# RoboRio_LED_THOLE_schematic.net
KiCad netlist of a schematic drawn in EAGLE
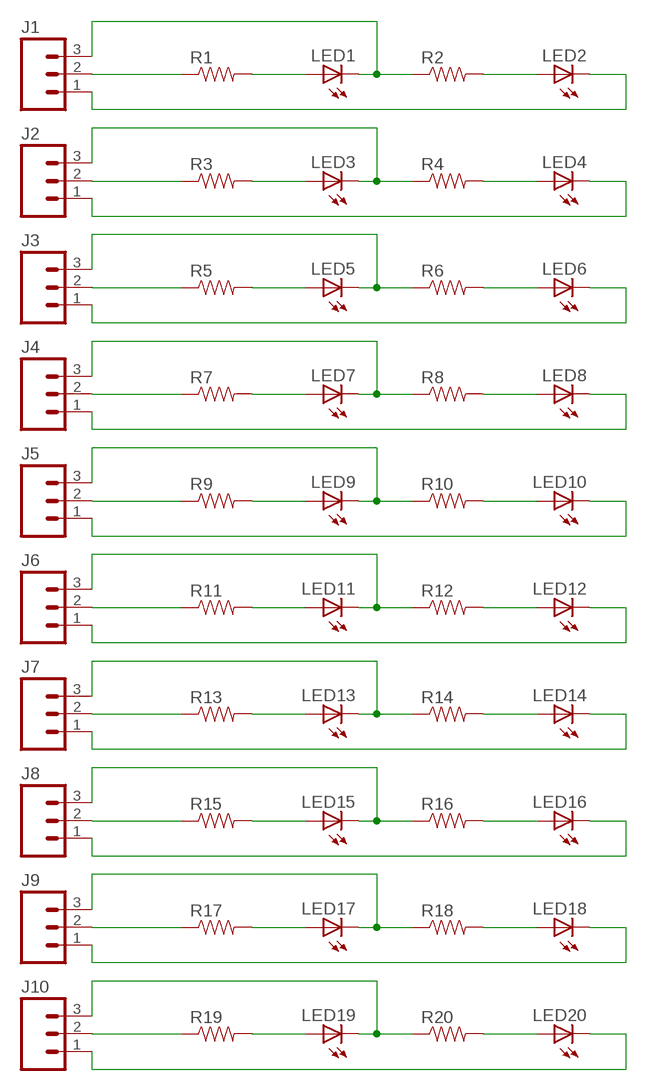
[diagram p0: schematic, sheet 1]

(export (version "E")
  (design (tool "Eeschema 10.0.6"))
  (components
    (comp (ref "J1")
      (value "M03PTH")
      (footprint "eagle-import:1X03")
      (libsource (lib "eagle-import") (part "M03PTH"))
    )
    (comp (ref "J2")
      (value "M03PTH")
      (footprint "eagle-import:1X03")
      (libsource (lib "eagle-import") (part "M03PTH"))
    )
    (comp (ref "J3")
      (value "M03PTH")
      (footprint "eagle-import:1X03")
      (libsource (lib "eagle-import") (part "M03PTH"))
    )
    (comp (ref "J4")
      (value "M03PTH")
      (footprint "eagle-import:1X03")
      (libsource (lib "eagle-import") (part "M03PTH"))
    )
    (comp (ref "J5")
      (value "M03PTH")
      (footprint "eagle-import:1X03")
      (libsource (lib "eagle-import") (part "M03PTH"))
    )
    (comp (ref "J6")
      (value "M03PTH")
      (footprint "eagle-import:1X03")
      (libsource (lib "eagle-import") (part "M03PTH"))
    )
    (comp (ref "J7")
      (value "M03PTH")
      (footprint "eagle-import:1X03")
      (libsource (lib "eagle-import") (part "M03PTH"))
    )
    (comp (ref "J8")
      (value "M03PTH")
      (footprint "eagle-import:1X03")
      (libsource (lib "eagle-import") (part "M03PTH"))
    )
    (comp (ref "J9")
      (value "M03PTH")
      (footprint "eagle-import:1X03")
      (libsource (lib "eagle-import") (part "M03PTH"))
    )
    (comp (ref "J10")
      (value "M03PTH")
      (footprint "eagle-import:1X03")
      (libsource (lib "eagle-import") (part "M03PTH"))
    )
    (comp (ref "LED1")
      (value "LED3MM")
      (footprint "eagle-import:LED3MM")
      (libsource (lib "eagle-import") (part "LED3MM"))
    )
    (comp (ref "LED2")
      (value "LED3MM")
      (footprint "eagle-import:LED3MM")
      (libsource (lib "eagle-import") (part "LED3MM"))
    )
    (comp (ref "LED3")
      (value "LED3MM")
      (footprint "eagle-import:LED3MM")
      (libsource (lib "eagle-import") (part "LED3MM"))
    )
    (comp (ref "LED4")
      (value "LED3MM")
      (footprint "eagle-import:LED3MM")
      (libsource (lib "eagle-import") (part "LED3MM"))
    )
    (comp (ref "LED5")
      (value "LED3MM")
      (footprint "eagle-import:LED3MM")
      (libsource (lib "eagle-import") (part "LED3MM"))
    )
    (comp (ref "LED6")
      (value "LED3MM")
      (footprint "eagle-import:LED3MM")
      (libsource (lib "eagle-import") (part "LED3MM"))
    )
    (comp (ref "LED7")
      (value "LED3MM")
      (footprint "eagle-import:LED3MM")
      (libsource (lib "eagle-import") (part "LED3MM"))
    )
    (comp (ref "LED8")
      (value "LED3MM")
      (footprint "eagle-import:LED3MM")
      (libsource (lib "eagle-import") (part "LED3MM"))
    )
    (comp (ref "LED9")
      (value "LED3MM")
      (footprint "eagle-import:LED3MM")
      (libsource (lib "eagle-import") (part "LED3MM"))
    )
    (comp (ref "LED10")
      (value "LED3MM")
      (footprint "eagle-import:LED3MM")
      (libsource (lib "eagle-import") (part "LED3MM"))
    )
    (comp (ref "LED11")
      (value "LED3MM")
      (footprint "eagle-import:LED3MM")
      (libsource (lib "eagle-import") (part "LED3MM"))
    )
    (comp (ref "LED12")
      (value "LED3MM")
      (footprint "eagle-import:LED3MM")
      (libsource (lib "eagle-import") (part "LED3MM"))
    )
    (comp (ref "LED13")
      (value "LED3MM")
      (footprint "eagle-import:LED3MM")
      (libsource (lib "eagle-import") (part "LED3MM"))
    )
    (comp (ref "LED14")
      (value "LED3MM")
      (footprint "eagle-import:LED3MM")
      (libsource (lib "eagle-import") (part "LED3MM"))
    )
    (comp (ref "LED15")
      (value "LED3MM")
      (footprint "eagle-import:LED3MM")
      (libsource (lib "eagle-import") (part "LED3MM"))
    )
    (comp (ref "LED16")
      (value "LED3MM")
      (footprint "eagle-import:LED3MM")
      (libsource (lib "eagle-import") (part "LED3MM"))
    )
    (comp (ref "LED17")
      (value "LED3MM")
      (footprint "eagle-import:LED3MM")
      (libsource (lib "eagle-import") (part "LED3MM"))
    )
    (comp (ref "LED18")
      (value "LED3MM")
      (footprint "eagle-import:LED3MM")
      (libsource (lib "eagle-import") (part "LED3MM"))
    )
    (comp (ref "LED19")
      (value "LED3MM")
      (footprint "eagle-import:LED3MM")
      (libsource (lib "eagle-import") (part "LED3MM"))
    )
    (comp (ref "LED20")
      (value "LED3MM")
      (footprint "eagle-import:LED3MM")
      (libsource (lib "eagle-import") (part "LED3MM"))
    )
    (comp (ref "R1")
      (value "RESISTORKIT")
      (footprint "eagle-import:AXIAL-0.3-KIT")
      (libsource (lib "eagle-import") (part "RESISTORKIT"))
    )
    (comp (ref "R2")
      (value "RESISTORKIT")
      (footprint "eagle-import:AXIAL-0.3-KIT")
      (libsource (lib "eagle-import") (part "RESISTORKIT"))
    )
    (comp (ref "R3")
      (value "RESISTORKIT")
      (footprint "eagle-import:AXIAL-0.3-KIT")
      (libsource (lib "eagle-import") (part "RESISTORKIT"))
    )
    (comp (ref "R4")
      (value "RESISTORKIT")
      (footprint "eagle-import:AXIAL-0.3-KIT")
      (libsource (lib "eagle-import") (part "RESISTORKIT"))
    )
    (comp (ref "R5")
      (value "RESISTORKIT")
      (footprint "eagle-import:AXIAL-0.3-KIT")
      (libsource (lib "eagle-import") (part "RESISTORKIT"))
    )
    (comp (ref "R6")
      (value "RESISTORKIT")
      (footprint "eagle-import:AXIAL-0.3-KIT")
      (libsource (lib "eagle-import") (part "RESISTORKIT"))
    )
    (comp (ref "R7")
      (value "RESISTORKIT")
      (footprint "eagle-import:AXIAL-0.3-KIT")
      (libsource (lib "eagle-import") (part "RESISTORKIT"))
    )
    (comp (ref "R8")
      (value "RESISTORKIT")
      (footprint "eagle-import:AXIAL-0.3-KIT")
      (libsource (lib "eagle-import") (part "RESISTORKIT"))
    )
    (comp (ref "R9")
      (value "RESISTORKIT")
      (footprint "eagle-import:AXIAL-0.3-KIT")
      (libsource (lib "eagle-import") (part "RESISTORKIT"))
    )
    (comp (ref "R10")
      (value "RESISTORKIT")
      (footprint "eagle-import:AXIAL-0.3-KIT")
      (libsource (lib "eagle-import") (part "RESISTORKIT"))
    )
    (comp (ref "R11")
      (value "RESISTORKIT")
      (footprint "eagle-import:AXIAL-0.3-KIT")
      (libsource (lib "eagle-import") (part "RESISTORKIT"))
    )
    (comp (ref "R12")
      (value "RESISTORKIT")
      (footprint "eagle-import:AXIAL-0.3-KIT")
      (libsource (lib "eagle-import") (part "RESISTORKIT"))
    )
    (comp (ref "R13")
      (value "RESISTORKIT")
      (footprint "eagle-import:AXIAL-0.3-KIT")
      (libsource (lib "eagle-import") (part "RESISTORKIT"))
    )
    (comp (ref "R14")
      (value "RESISTORKIT")
      (footprint "eagle-import:AXIAL-0.3-KIT")
      (libsource (lib "eagle-import") (part "RESISTORKIT"))
    )
    (comp (ref "R15")
      (value "RESISTORKIT")
      (footprint "eagle-import:AXIAL-0.3-KIT")
      (libsource (lib "eagle-import") (part "RESISTORKIT"))
    )
    (comp (ref "R16")
      (value "RESISTORKIT")
      (footprint "eagle-import:AXIAL-0.3-KIT")
      (libsource (lib "eagle-import") (part "RESISTORKIT"))
    )
    (comp (ref "R17")
      (value "RESISTORKIT")
      (footprint "eagle-import:AXIAL-0.3-KIT")
      (libsource (lib "eagle-import") (part "RESISTORKIT"))
    )
    (comp (ref "R18")
      (value "RESISTORKIT")
      (footprint "eagle-import:AXIAL-0.3-KIT")
      (libsource (lib "eagle-import") (part "RESISTORKIT"))
    )
    (comp (ref "R19")
      (value "RESISTORKIT")
      (footprint "eagle-import:AXIAL-0.3-KIT")
      (libsource (lib "eagle-import") (part "RESISTORKIT"))
    )
    (comp (ref "R20")
      (value "RESISTORKIT")
      (footprint "eagle-import:AXIAL-0.3-KIT")
      (libsource (lib "eagle-import") (part "RESISTORKIT"))
    )
  )
  (nets
    (net (code "1") (name "Net-(LED1-C)") (class "Default")
      (node (ref "J1") (pin "3") (pinfunction "3_3") (pintype "passive"))
      (node (ref "LED1") (pin "K") (pinfunction "C_K") (pintype "passive"))
      (node (ref "R2") (pin "P$1") (pinfunction "1_P$1") (pintype "passive"))
    )
    (net (code "2") (name "Net-(LED2-C)") (class "Default")
      (node (ref "J1") (pin "1") (pinfunction "1_1") (pintype "passive"))
      (node (ref "LED2") (pin "K") (pinfunction "C_K") (pintype "passive"))
    )
    (net (code "3") (name "Net-(LED3-C)") (class "Default")
      (node (ref "J2") (pin "3") (pinfunction "3_3") (pintype "passive"))
      (node (ref "LED3") (pin "K") (pinfunction "C_K") (pintype "passive"))
      (node (ref "R4") (pin "P$1") (pinfunction "1_P$1") (pintype "passive"))
    )
    (net (code "4") (name "Net-(LED4-C)") (class "Default")
      (node (ref "J2") (pin "1") (pinfunction "1_1") (pintype "passive"))
      (node (ref "LED4") (pin "K") (pinfunction "C_K") (pintype "passive"))
    )
    (net (code "5") (name "Net-(LED5-C)") (class "Default")
      (node (ref "J3") (pin "3") (pinfunction "3_3") (pintype "passive"))
      (node (ref "LED5") (pin "K") (pinfunction "C_K") (pintype "passive"))
      (node (ref "R6") (pin "P$1") (pinfunction "1_P$1") (pintype "passive"))
    )
    (net (code "6") (name "Net-(LED6-C)") (class "Default")
      (node (ref "J3") (pin "1") (pinfunction "1_1") (pintype "passive"))
      (node (ref "LED6") (pin "K") (pinfunction "C_K") (pintype "passive"))
    )
    (net (code "7") (name "Net-(LED7-C)") (class "Default")
      (node (ref "J4") (pin "3") (pinfunction "3_3") (pintype "passive"))
      (node (ref "LED7") (pin "K") (pinfunction "C_K") (pintype "passive"))
      (node (ref "R8") (pin "P$1") (pinfunction "1_P$1") (pintype "passive"))
    )
    (net (code "8") (name "Net-(LED8-C)") (class "Default")
      (node (ref "J4") (pin "1") (pinfunction "1_1") (pintype "passive"))
      (node (ref "LED8") (pin "K") (pinfunction "C_K") (pintype "passive"))
    )
    (net (code "9") (name "Net-(LED9-C)") (class "Default")
      (node (ref "J5") (pin "3") (pinfunction "3_3") (pintype "passive"))
      (node (ref "LED9") (pin "K") (pinfunction "C_K") (pintype "passive"))
      (node (ref "R10") (pin "P$1") (pinfunction "1_P$1") (pintype "passive"))
    )
    (net (code "10") (name "Net-(LED10-C)") (class "Default")
      (node (ref "J5") (pin "1") (pinfunction "1_1") (pintype "passive"))
      (node (ref "LED10") (pin "K") (pinfunction "C_K") (pintype "passive"))
    )
    (net (code "11") (name "Net-(LED11-C)") (class "Default")
      (node (ref "J6") (pin "3") (pinfunction "3_3") (pintype "passive"))
      (node (ref "LED11") (pin "K") (pinfunction "C_K") (pintype "passive"))
      (node (ref "R12") (pin "P$1") (pinfunction "1_P$1") (pintype "passive"))
    )
    (net (code "12") (name "Net-(LED12-C)") (class "Default")
      (node (ref "J6") (pin "1") (pinfunction "1_1") (pintype "passive"))
      (node (ref "LED12") (pin "K") (pinfunction "C_K") (pintype "passive"))
    )
    (net (code "13") (name "Net-(LED13-C)") (class "Default")
      (node (ref "J7") (pin "3") (pinfunction "3_3") (pintype "passive"))
      (node (ref "LED13") (pin "K") (pinfunction "C_K") (pintype "passive"))
      (node (ref "R14") (pin "P$1") (pinfunction "1_P$1") (pintype "passive"))
    )
    (net (code "14") (name "Net-(LED14-C)") (class "Default")
      (node (ref "J7") (pin "1") (pinfunction "1_1") (pintype "passive"))
      (node (ref "LED14") (pin "K") (pinfunction "C_K") (pintype "passive"))
    )
    (net (code "15") (name "Net-(LED15-C)") (class "Default")
      (node (ref "J8") (pin "3") (pinfunction "3_3") (pintype "passive"))
      (node (ref "LED15") (pin "K") (pinfunction "C_K") (pintype "passive"))
      (node (ref "R16") (pin "P$1") (pinfunction "1_P$1") (pintype "passive"))
    )
    (net (code "16") (name "Net-(LED16-C)") (class "Default")
      (node (ref "J8") (pin "1") (pinfunction "1_1") (pintype "passive"))
      (node (ref "LED16") (pin "K") (pinfunction "C_K") (pintype "passive"))
    )
    (net (code "17") (name "Net-(LED17-C)") (class "Default")
      (node (ref "J9") (pin "3") (pinfunction "3_3") (pintype "passive"))
      (node (ref "LED17") (pin "K") (pinfunction "C_K") (pintype "passive"))
      (node (ref "R18") (pin "P$1") (pinfunction "1_P$1") (pintype "passive"))
    )
    (net (code "18") (name "Net-(LED18-C)") (class "Default")
      (node (ref "J9") (pin "1") (pinfunction "1_1") (pintype "passive"))
      (node (ref "LED18") (pin "K") (pinfunction "C_K") (pintype "passive"))
    )
    (net (code "19") (name "Net-(LED19-C)") (class "Default")
      (node (ref "J10") (pin "3") (pinfunction "3_3") (pintype "passive"))
      (node (ref "LED19") (pin "K") (pinfunction "C_K") (pintype "passive"))
      (node (ref "R20") (pin "P$1") (pinfunction "1_P$1") (pintype "passive"))
    )
    (net (code "20") (name "Net-(LED20-C)") (class "Default")
      (node (ref "J10") (pin "1") (pinfunction "1_1") (pintype "passive"))
      (node (ref "LED20") (pin "K") (pinfunction "C_K") (pintype "passive"))
    )
    (net (code "21") (name "Net-(R1-1)") (class "Default")
      (node (ref "J1") (pin "2") (pinfunction "2_2") (pintype "passive"))
      (node (ref "R1") (pin "P$1") (pinfunction "1_P$1") (pintype "passive"))
    )
    (net (code "22") (name "Net-(R1-2)") (class "Default")
      (node (ref "LED1") (pin "A") (pinfunction "A_A") (pintype "passive"))
      (node (ref "R1") (pin "P$2") (pinfunction "2_P$2") (pintype "passive"))
    )
    (net (code "23") (name "Net-(R2-2)") (class "Default")
      (node (ref "LED2") (pin "A") (pinfunction "A_A") (pintype "passive"))
      (node (ref "R2") (pin "P$2") (pinfunction "2_P$2") (pintype "passive"))
    )
    (net (code "24") (name "Net-(R3-1)") (class "Default")
      (node (ref "J2") (pin "2") (pinfunction "2_2") (pintype "passive"))
      (node (ref "R3") (pin "P$1") (pinfunction "1_P$1") (pintype "passive"))
    )
    (net (code "25") (name "Net-(R3-2)") (class "Default")
      (node (ref "LED3") (pin "A") (pinfunction "A_A") (pintype "passive"))
      (node (ref "R3") (pin "P$2") (pinfunction "2_P$2") (pintype "passive"))
    )
    (net (code "26") (name "Net-(R4-2)") (class "Default")
      (node (ref "LED4") (pin "A") (pinfunction "A_A") (pintype "passive"))
      (node (ref "R4") (pin "P$2") (pinfunction "2_P$2") (pintype "passive"))
    )
    (net (code "27") (name "Net-(R5-1)") (class "Default")
      (node (ref "J3") (pin "2") (pinfunction "2_2") (pintype "passive"))
      (node (ref "R5") (pin "P$1") (pinfunction "1_P$1") (pintype "passive"))
    )
    (net (code "28") (name "Net-(R5-2)") (class "Default")
      (node (ref "LED5") (pin "A") (pinfunction "A_A") (pintype "passive"))
      (node (ref "R5") (pin "P$2") (pinfunction "2_P$2") (pintype "passive"))
    )
    (net (code "29") (name "Net-(R6-2)") (class "Default")
      (node (ref "LED6") (pin "A") (pinfunction "A_A") (pintype "passive"))
      (node (ref "R6") (pin "P$2") (pinfunction "2_P$2") (pintype "passive"))
    )
    (net (code "30") (name "Net-(R7-1)") (class "Default")
      (node (ref "J4") (pin "2") (pinfunction "2_2") (pintype "passive"))
      (node (ref "R7") (pin "P$1") (pinfunction "1_P$1") (pintype "passive"))
    )
    (net (code "31") (name "Net-(R7-2)") (class "Default")
      (node (ref "LED7") (pin "A") (pinfunction "A_A") (pintype "passive"))
      (node (ref "R7") (pin "P$2") (pinfunction "2_P$2") (pintype "passive"))
    )
    (net (code "32") (name "Net-(R8-2)") (class "Default")
      (node (ref "LED8") (pin "A") (pinfunction "A_A") (pintype "passive"))
      (node (ref "R8") (pin "P$2") (pinfunction "2_P$2") (pintype "passive"))
    )
    (net (code "33") (name "Net-(R9-1)") (class "Default")
      (node (ref "J5") (pin "2") (pinfunction "2_2") (pintype "passive"))
      (node (ref "R9") (pin "P$1") (pinfunction "1_P$1") (pintype "passive"))
    )
    (net (code "34") (name "Net-(R9-2)") (class "Default")
      (node (ref "LED9") (pin "A") (pinfunction "A_A") (pintype "passive"))
      (node (ref "R9") (pin "P$2") (pinfunction "2_P$2") (pintype "passive"))
    )
    (net (code "35") (name "Net-(R10-2)") (class "Default")
      (node (ref "LED10") (pin "A") (pinfunction "A_A") (pintype "passive"))
      (node (ref "R10") (pin "P$2") (pinfunction "2_P$2") (pintype "passive"))
    )
    (net (code "36") (name "Net-(R11-1)") (class "Default")
      (node (ref "J6") (pin "2") (pinfunction "2_2") (pintype "passive"))
      (node (ref "R11") (pin "P$1") (pinfunction "1_P$1") (pintype "passive"))
    )
    (net (code "37") (name "Net-(R11-2)") (class "Default")
      (node (ref "LED11") (pin "A") (pinfunction "A_A") (pintype "passive"))
      (node (ref "R11") (pin "P$2") (pinfunction "2_P$2") (pintype "passive"))
    )
    (net (code "38") (name "Net-(R12-2)") (class "Default")
      (node (ref "LED12") (pin "A") (pinfunction "A_A") (pintype "passive"))
      (node (ref "R12") (pin "P$2") (pinfunction "2_P$2") (pintype "passive"))
    )
    (net (code "39") (name "Net-(R13-1)") (class "Default")
      (node (ref "J7") (pin "2") (pinfunction "2_2") (pintype "passive"))
      (node (ref "R13") (pin "P$1") (pinfunction "1_P$1") (pintype "passive"))
    )
    (net (code "40") (name "Net-(R13-2)") (class "Default")
      (node (ref "LED13") (pin "A") (pinfunction "A_A") (pintype "passive"))
      (node (ref "R13") (pin "P$2") (pinfunction "2_P$2") (pintype "passive"))
    )
    (net (code "41") (name "Net-(R14-2)") (class "Default")
      (node (ref "LED14") (pin "A") (pinfunction "A_A") (pintype "passive"))
      (node (ref "R14") (pin "P$2") (pinfunction "2_P$2") (pintype "passive"))
    )
    (net (code "42") (name "Net-(R15-1)") (class "Default")
      (node (ref "J8") (pin "2") (pinfunction "2_2") (pintype "passive"))
      (node (ref "R15") (pin "P$1") (pinfunction "1_P$1") (pintype "passive"))
    )
    (net (code "43") (name "Net-(R15-2)") (class "Default")
      (node (ref "LED15") (pin "A") (pinfunction "A_A") (pintype "passive"))
      (node (ref "R15") (pin "P$2") (pinfunction "2_P$2") (pintype "passive"))
    )
    (net (code "44") (name "Net-(R16-2)") (class "Default")
      (node (ref "LED16") (pin "A") (pinfunction "A_A") (pintype "passive"))
      (node (ref "R16") (pin "P$2") (pinfunction "2_P$2") (pintype "passive"))
    )
    (net (code "45") (name "Net-(R17-1)") (class "Default")
      (node (ref "J9") (pin "2") (pinfunction "2_2") (pintype "passive"))
      (node (ref "R17") (pin "P$1") (pinfunction "1_P$1") (pintype "passive"))
    )
    (net (code "46") (name "Net-(R17-2)") (class "Default")
      (node (ref "LED17") (pin "A") (pinfunction "A_A") (pintype "passive"))
      (node (ref "R17") (pin "P$2") (pinfunction "2_P$2") (pintype "passive"))
    )
    (net (code "47") (name "Net-(R18-2)") (class "Default")
      (node (ref "LED18") (pin "A") (pinfunction "A_A") (pintype "passive"))
      (node (ref "R18") (pin "P$2") (pinfunction "2_P$2") (pintype "passive"))
    )
    (net (code "48") (name "Net-(R19-1)") (class "Default")
      (node (ref "J10") (pin "2") (pinfunction "2_2") (pintype "passive"))
      (node (ref "R19") (pin "P$1") (pinfunction "1_P$1") (pintype "passive"))
    )
    (net (code "49") (name "Net-(R19-2)") (class "Default")
      (node (ref "LED19") (pin "A") (pinfunction "A_A") (pintype "passive"))
      (node (ref "R19") (pin "P$2") (pinfunction "2_P$2") (pintype "passive"))
    )
    (net (code "50") (name "Net-(R20-2)") (class "Default")
      (node (ref "LED20") (pin "A") (pinfunction "A_A") (pintype "passive"))
      (node (ref "R20") (pin "P$2") (pinfunction "2_P$2") (pintype "passive"))
    )
  )
)
